# User_Port.net
KiCad netlist of a schematic drawn in EAGLE
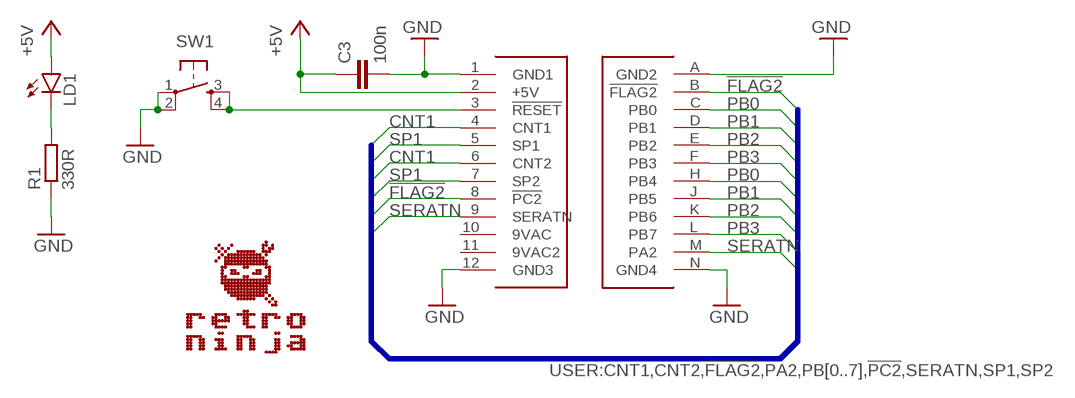
[diagram p0: schematic, sheet 1]

(export (version "E")
  (design (tool "Eeschema 10.0.6"))
  (components
    (comp (ref "C3")
      (value "100n")
      (footprint "eagle-import:C0805")
      (libsource (lib "eagle-import") (part "C-EUC0805"))
    )
    (comp (ref "LD1")
      (value "LED3MM")
      (footprint "eagle-import:LED3MM")
      (libsource (lib "eagle-import") (part "LED3MM"))
    )
    (comp (ref "R1")
      (value "330R")
      (footprint "eagle-import:R0805")
      (libsource (lib "eagle-import") (part "R-EU_R0805"))
    )
    (comp (ref "SW1")
      (value "TAC_SWITCHPTH")
      (footprint "eagle-import:TACTILE-PTH")
      (libsource (lib "eagle-import") (part "TAC_SWITCHPTH"))
    )
    (comp (ref "U$1")
      (value "RETRONINJA_TEXT")
      (footprint "eagle-import:RETRONINJA_TEXT_17MM")
      (libsource (lib "eagle-import") (part "RETRONINJA_TEXT"))
    )
    (comp (ref "X1")
      (value "C64_USER_PORT_CONNECTOR_SIDE")
      (footprint "eagle-import:C64_USER_PORT_DEVICE_CONNECTOR")
      (libsource (lib "eagle-import") (part "C64_USER_PORT_CONNECTOR_SIDE"))
    )
  )
  (nets
    (net (code "6") (name "+5V") (class "Default")
      (node (ref "C3") (pin "1") (pinfunction "1_1") (pintype "passive"))
      (node (ref "LD1") (pin "A") (pinfunction "A_A") (pintype "passive"))
      (node (ref "X1") (pin "2") (pinfunction "+5V_2") (pintype "power_in"))
    )
    (net (code "7") (name "/9VAC") (class "Default")
      (node (ref "X1") (pin "10") (pinfunction "9VAC_10") (pintype "power_in"))
    )
    (net (code "8") (name "/9VAC2") (class "Default")
      (node (ref "X1") (pin "11") (pinfunction "9VAC2_11") (pintype "power_in"))
    )
    (net (code "9") (name "/CNT1") (class "Default")
      (node (ref "X1") (pin "4") (pinfunction "CNT1_4") (pintype "bidirectional"))
      (node (ref "X1") (pin "6") (pinfunction "CNT2_6") (pintype "bidirectional"))
    )
    (net (code "10") (name "/PB0") (class "Default")
      (node (ref "X1") (pin "C") (pinfunction "PB0_C") (pintype "bidirectional"))
      (node (ref "X1") (pin "H") (pinfunction "PB4_H") (pintype "bidirectional"))
    )
    (net (code "11") (name "/PB1") (class "Default")
      (node (ref "X1") (pin "D") (pinfunction "PB1_D") (pintype "bidirectional"))
      (node (ref "X1") (pin "J") (pinfunction "PB5_J") (pintype "bidirectional"))
    )
    (net (code "12") (name "/PB2") (class "Default")
      (node (ref "X1") (pin "E") (pinfunction "PB2_E") (pintype "bidirectional"))
      (node (ref "X1") (pin "K") (pinfunction "PB6_K") (pintype "bidirectional"))
    )
    (net (code "13") (name "/PB3") (class "Default")
      (node (ref "X1") (pin "F") (pinfunction "PB3_F") (pintype "bidirectional"))
      (node (ref "X1") (pin "L") (pinfunction "PB7_L") (pintype "bidirectional"))
    )
    (net (code "14") (name "/SERATN") (class "Default")
      (node (ref "X1") (pin "9") (pinfunction "SERATN_9") (pintype "input"))
      (node (ref "X1") (pin "M") (pinfunction "PA2_M") (pintype "bidirectional"))
    )
    (net (code "15") (name "/SP1") (class "Default")
      (node (ref "X1") (pin "5") (pinfunction "SP1_5") (pintype "bidirectional"))
      (node (ref "X1") (pin "7") (pinfunction "SP2_7") (pintype "bidirectional"))
    )
    (net (code "17") (name "/~{FLAG2}") (class "Default")
      (node (ref "X1") (pin "8") (pinfunction "~{PC2}_8") (pintype "bidirectional"))
      (node (ref "X1") (pin "B") (pinfunction "~{FLAG2}_B") (pintype "bidirectional"))
    )
    (net (code "18") (name "GND") (class "Default")
      (node (ref "C3") (pin "2") (pinfunction "2_2") (pintype "passive"))
      (node (ref "R1") (pin "1") (pinfunction "1_1") (pintype "passive"))
      (node (ref "SW1") (pin "1") (pinfunction "1_1") (pintype "passive"))
      (node (ref "SW1") (pin "2") (pinfunction "2_2") (pintype "passive"))
      (node (ref "X1") (pin "1") (pinfunction "GND1_1") (pintype "power_in"))
      (node (ref "X1") (pin "12") (pinfunction "GND3_12") (pintype "power_in"))
      (node (ref "X1") (pin "A") (pinfunction "GND2_A") (pintype "power_in"))
      (node (ref "X1") (pin "N") (pinfunction "GND4_N") (pintype "power_in"))
    )
    (net (code "19") (name "Net-(LD1-C)") (class "Default")
      (node (ref "LD1") (pin "K") (pinfunction "C_K") (pintype "passive"))
      (node (ref "R1") (pin "2") (pinfunction "2_2") (pintype "passive"))
    )
    (net (code "20") (name "Net-(X1-~{RESET})") (class "Default")
      (node (ref "SW1") (pin "3") (pinfunction "3_3") (pintype "passive"))
      (node (ref "SW1") (pin "4") (pinfunction "4_4") (pintype "passive"))
      (node (ref "X1") (pin "3") (pinfunction "~{RESET}_3") (pintype "bidirectional"))
    )
  )
)
